# Slave.net
KiCad netlist of a schematic drawn in Altium Designer
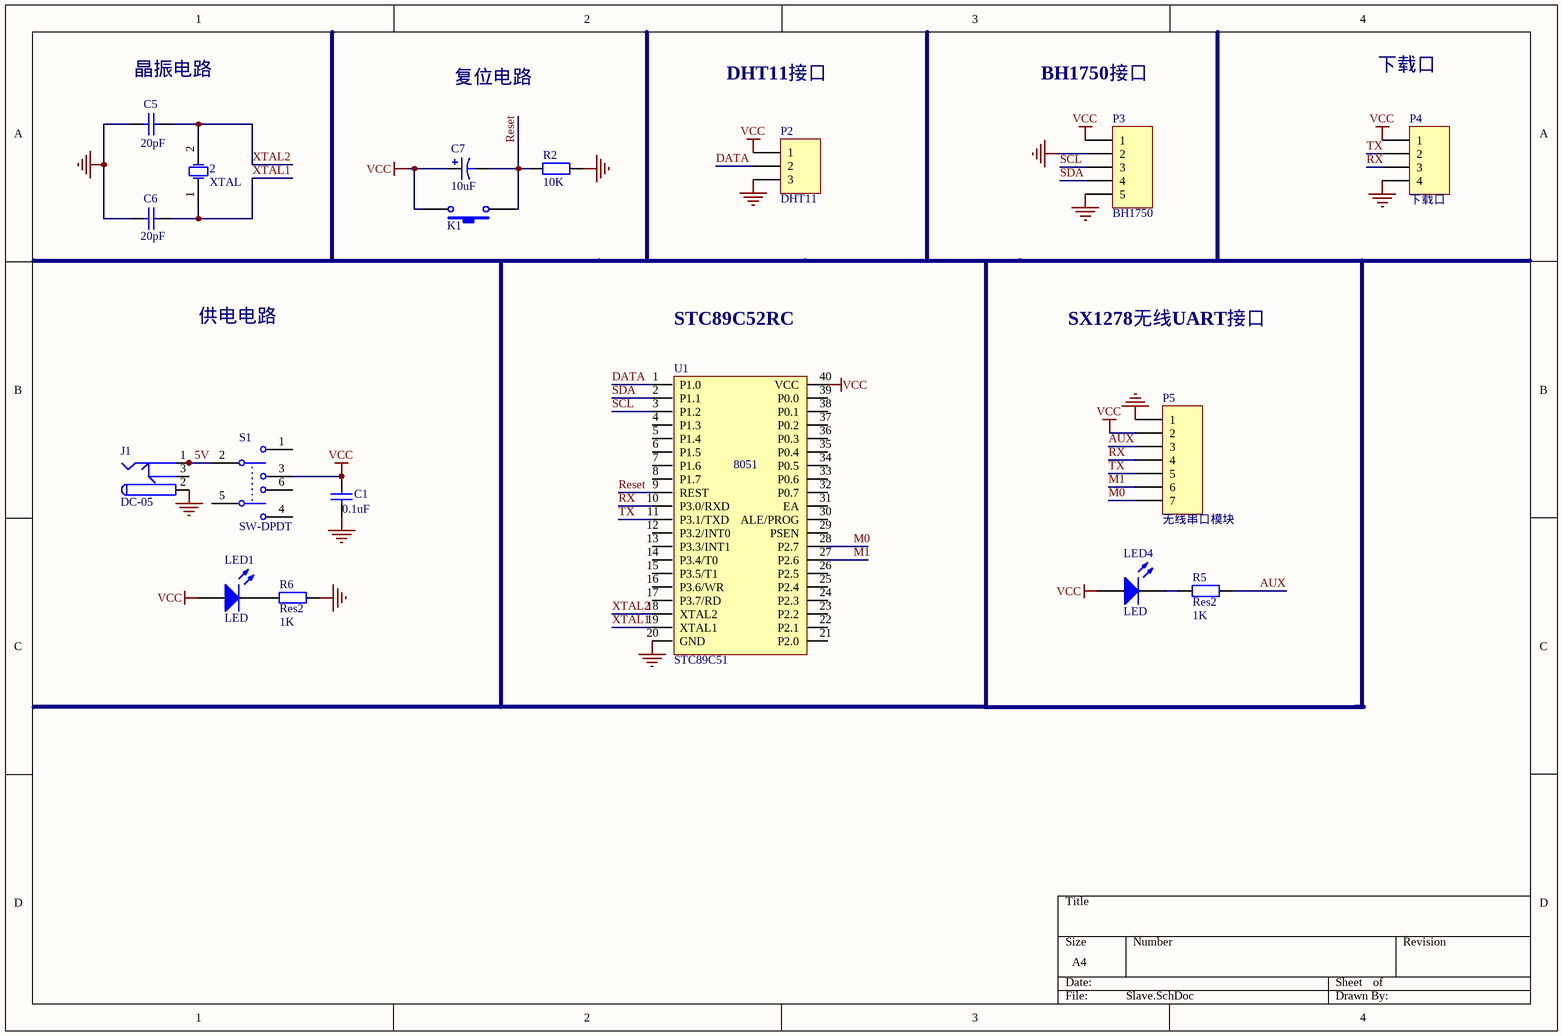
[diagram p0: Slave.SchDoc]

(export (version "E")
  (design (tool "Eeschema 10.0.6"))
  (components
    (comp (ref "2")
      (value "XTAL")
      (footprint "XTAL_US")
      (description "Crystal Oscillator")
      (fields (field (name "PUBLISHER") "Altium Limited"))
      (libsource (lib "Miscellaneous Devices") (part "XTAL"))
    )
    (comp (ref "C1")
      (value "0.1uF")
      (footprint "RAD-0.1")
      (description "Capacitor")
      (fields (field (name "Comment") "Cap") (field (name "PUBLISHER") "Altium Limited"))
      (libsource (lib "Miscellaneous Devices") (part "Cap"))
    )
    (comp (ref "C5")
      (value "20pF")
      (footprint "RAD-0.1")
      (description "Capacitor")
      (fields (field (name "Comment") "Cap") (field (name "PUBLISHER") "Altium Limited"))
      (libsource (lib "Miscellaneous Devices") (part "Cap"))
    )
    (comp (ref "C6")
      (value "20pF")
      (footprint "RAD-0.1")
      (description "Capacitor")
      (fields (field (name "Comment") "Cap") (field (name "PUBLISHER") "Altium Limited"))
      (libsource (lib "Miscellaneous Devices") (part "Cap"))
    )
    (comp (ref "C7")
      (value "10uF")
      (footprint "RB.1/.2")
      (description "Polarized Capacitor (Radial)")
      (fields (field (name "Comment") "Cap Pol1") (field (name "PUBLISHER") "Altium Limited"))
      (libsource (lib "Miscellaneous Devices") (part "Cap Pol1"))
    )
    (comp (ref "J1") (value "DC-05") (footprint "DC-05") (libsource (lib "My library") (part "DC-05")))
    (comp (ref "K1") (value "四脚按键") (footprint "四脚按键") (libsource (lib "My library") (part "四脚按键")))
    (comp (ref "LED1") (value "LED") (footprint "LED") (libsource (lib "My library") (part "LED")))
    (comp (ref "LED4") (value "LED") (footprint "LED") (libsource (lib "My library") (part "LED")))
    (comp (ref "P2")
      (value "DHT11")
      (footprint "HDR1X3")
      (description "Header, 3-Pin")
      (fields (field (name "PUBLISHER") "Altium Limited"))
      (libsource (lib "Miscellaneous Connectors") (part "Header 3"))
    )
    (comp (ref "P3")
      (value "BH1750")
      (footprint "HDR1X5")
      (description "Header, 5-Pin")
      (fields (field (name "PUBLISHER") "Altium Limited"))
      (libsource (lib "Miscellaneous Connectors") (part "Header 5"))
    )
    (comp (ref "P4")
      (value "下载口")
      (footprint "HDR1X4")
      (description "Header, 4-Pin")
      (fields (field (name "PUBLISHER") "Altium Limited"))
      (libsource (lib "Miscellaneous Connectors") (part "Header 4"))
    )
    (comp (ref "P5")
      (value "无线串口模块")
      (footprint "AS32-TTL-100")
      (description "Header, 7-Pin")
      (fields (field (name "PUBLISHER") "Altium Limited"))
      (libsource (lib "Miscellaneous Connectors") (part "Header 7"))
    )
    (comp (ref "R2")
      (value "10K")
      (footprint "AXIAL-0.4")
      (description "Resistor")
      (fields (field (name "Comment") "Res2") (field (name "PUBLISHER") "Altium Limited"))
      (libsource (lib "Miscellaneous Devices") (part "Res2"))
    )
    (comp (ref "R5")
      (value "Res2")
      (footprint "AXIAL-0.4")
      (description "Resistor")
      (fields (field (name "ALTIUM_VALUE") "1K") (field (name "PUBLISHER") "Altium Limited"))
      (libsource (lib "Miscellaneous Devices") (part "Res2"))
    )
    (comp (ref "R6")
      (value "Res2")
      (footprint "AXIAL-0.4")
      (description "Resistor")
      (fields (field (name "ALTIUM_VALUE") "1K") (field (name "PUBLISHER") "Altium Limited"))
      (libsource (lib "Miscellaneous Devices") (part "Res2"))
    )
    (comp (ref "S1")
      (value "SW-DPDT")
      (footprint "SWITCH_B1")
      (description "单刀双掷开关")
      (fields (field (name "PUBLISHER") "Altium Limited"))
      (libsource (lib "Fszhang") (part "SW-DPDT"))
    )
    (comp (ref "U1") (value "STC89C51") (footprint "DIP-40") (libsource (lib "My library") (part "STC89C51")))
  )
  (nets
    (net (code "1") (name "/5V") (class "Default")
      (node (ref "J1") (pin "1") (pinfunction "1_1") (pintype "passive"))
      (node (ref "S1") (pin "2") (pinfunction "2_2") (pintype "passive"))
    )
    (net (code "2") (name "/AUX") (class "Default")
      (node (ref "P5") (pin "3") (pinfunction "3_3") (pintype "passive"))
      (node (ref "R5") (pin "2") (pinfunction "2_2") (pintype "passive"))
    )
    (net (code "3") (name "/DATA") (class "Default")
      (node (ref "P2") (pin "2") (pinfunction "2_2") (pintype "passive"))
      (node (ref "U1") (pin "1") (pinfunction "P1.0_1") (pintype "passive"))
    )
    (net (code "4") (name "/M0") (class "Default")
      (node (ref "P5") (pin "7") (pinfunction "7_7") (pintype "passive"))
      (node (ref "U1") (pin "28") (pinfunction "P2.7_28") (pintype "passive"))
    )
    (net (code "5") (name "/M1") (class "Default")
      (node (ref "P5") (pin "6") (pinfunction "6_6") (pintype "passive"))
      (node (ref "U1") (pin "27") (pinfunction "P2.6_27") (pintype "passive"))
    )
    (net (code "6") (name "/RX") (class "Default")
      (node (ref "P4") (pin "3") (pinfunction "3_3") (pintype "passive"))
      (node (ref "P5") (pin "4") (pinfunction "4_4") (pintype "passive"))
      (node (ref "U1") (pin "10") (pinfunction "P3.0/RXD_10") (pintype "passive"))
    )
    (net (code "7") (name "/Reset") (class "Default")
      (node (ref "C7") (pin "2") (pinfunction "2_2") (pintype "passive"))
      (node (ref "K1") (pin "1") (pinfunction "1_1") (pintype "passive"))
      (node (ref "R2") (pin "1") (pinfunction "1_1") (pintype "passive"))
      (node (ref "U1") (pin "9") (pinfunction "REST_9") (pintype "passive"))
    )
    (net (code "8") (name "/SCL") (class "Default")
      (node (ref "P3") (pin "3") (pinfunction "3_3") (pintype "passive"))
      (node (ref "U1") (pin "3") (pinfunction "P1.2_3") (pintype "passive"))
    )
    (net (code "9") (name "/SDA") (class "Default")
      (node (ref "P3") (pin "4") (pinfunction "4_4") (pintype "passive"))
      (node (ref "U1") (pin "2") (pinfunction "P1.1_2") (pintype "passive"))
    )
    (net (code "10") (name "/TX") (class "Default")
      (node (ref "P4") (pin "2") (pinfunction "2_2") (pintype "passive"))
      (node (ref "P5") (pin "5") (pinfunction "5_5") (pintype "passive"))
      (node (ref "U1") (pin "11") (pinfunction "P3.1/TXD_11") (pintype "passive"))
    )
    (net (code "11") (name "/XTAL1") (class "Default")
      (node (ref "2") (pin "1") (pinfunction "OSC1_1") (pintype "passive"))
      (node (ref "C6") (pin "2") (pinfunction "2_2") (pintype "passive"))
      (node (ref "U1") (pin "19") (pinfunction "XTAL1_19") (pintype "passive"))
    )
    (net (code "12") (name "/XTAL2") (class "Default")
      (node (ref "2") (pin "2") (pinfunction "OSC2_2") (pintype "passive"))
      (node (ref "C5") (pin "2") (pinfunction "2_2") (pintype "passive"))
      (node (ref "U1") (pin "18") (pinfunction "XTAL2_18") (pintype "passive"))
    )
    (net (code "13") (name "GND") (class "Default")
      (node (ref "C1") (pin "1") (pinfunction "1_1") (pintype "passive"))
      (node (ref "C5") (pin "1") (pinfunction "1_1") (pintype "passive"))
      (node (ref "C6") (pin "1") (pinfunction "1_1") (pintype "passive"))
      (node (ref "J1") (pin "2") (pinfunction "2_2") (pintype "passive"))
      (node (ref "P2") (pin "3") (pinfunction "3_3") (pintype "passive"))
      (node (ref "P3") (pin "2") (pinfunction "2_2") (pintype "passive"))
      (node (ref "P3") (pin "5") (pinfunction "5_5") (pintype "passive"))
      (node (ref "P4") (pin "4") (pinfunction "4_4") (pintype "passive"))
      (node (ref "P5") (pin "1") (pinfunction "1_1") (pintype "passive"))
      (node (ref "R2") (pin "2") (pinfunction "2_2") (pintype "passive"))
      (node (ref "R6") (pin "2") (pinfunction "2_2") (pintype "passive"))
      (node (ref "U1") (pin "20") (pinfunction "GND_20") (pintype "passive"))
    )
    (net (code "14") (name "Net-(LED1-Pad2)") (class "Default")
      (node (ref "LED1") (pin "2") (pinfunction "2_2") (pintype "passive"))
      (node (ref "R6") (pin "1") (pinfunction "1_1") (pintype "passive"))
    )
    (net (code "15") (name "Net-(LED4-Pad2)") (class "Default")
      (node (ref "LED4") (pin "2") (pinfunction "2_2") (pintype "passive"))
      (node (ref "R5") (pin "1") (pinfunction "1_1") (pintype "passive"))
    )
    (net (code "16") (name "VCC") (class "Default")
      (node (ref "C1") (pin "2") (pinfunction "2_2") (pintype "passive"))
      (node (ref "C7") (pin "1") (pinfunction "1_1") (pintype "passive"))
      (node (ref "K1") (pin "2") (pinfunction "2_2") (pintype "passive"))
      (node (ref "LED1") (pin "1") (pinfunction "1_1") (pintype "passive"))
      (node (ref "LED4") (pin "1") (pinfunction "1_1") (pintype "passive"))
      (node (ref "P2") (pin "1") (pinfunction "1_1") (pintype "passive"))
      (node (ref "P3") (pin "1") (pinfunction "1_1") (pintype "passive"))
      (node (ref "P4") (pin "1") (pinfunction "1_1") (pintype "passive"))
      (node (ref "P5") (pin "2") (pinfunction "2_2") (pintype "passive"))
      (node (ref "S1") (pin "3") (pinfunction "3_3") (pintype "passive"))
      (node (ref "U1") (pin "40") (pinfunction "VCC_40") (pintype "passive"))
    )
    (net (code "17") (name "unconnected-(J1-Pad3)") (class "Default")
      (node (ref "J1") (pin "3") (pinfunction "3_3") (pintype "passive"))
    )
    (net (code "18") (name "unconnected-(S1-Pad1)") (class "Default")
      (node (ref "S1") (pin "1") (pinfunction "1_1") (pintype "passive"))
    )
    (net (code "19") (name "unconnected-(S1-Pad4)") (class "Default")
      (node (ref "S1") (pin "4") (pinfunction "4_4") (pintype "passive"))
    )
    (net (code "20") (name "unconnected-(S1-Pad5)") (class "Default")
      (node (ref "S1") (pin "5") (pinfunction "5_5") (pintype "passive"))
    )
    (net (code "21") (name "unconnected-(S1-Pad6)") (class "Default")
      (node (ref "S1") (pin "6") (pinfunction "6_6") (pintype "passive"))
    )
    (net (code "22") (name "unconnected-(U1-ALE{slash}PROG-Pad30)") (class "Default")
      (node (ref "U1") (pin "30") (pinfunction "ALE/PROG_30") (pintype "passive"))
    )
    (net (code "23") (name "unconnected-(U1-EA-Pad31)") (class "Default")
      (node (ref "U1") (pin "31") (pinfunction "EA_31") (pintype "passive"))
    )
    (net (code "24") (name "unconnected-(U1-P0.0-Pad39)") (class "Default")
      (node (ref "U1") (pin "39") (pinfunction "P0.0_39") (pintype "passive"))
    )
    (net (code "25") (name "unconnected-(U1-P0.1-Pad38)") (class "Default")
      (node (ref "U1") (pin "38") (pinfunction "P0.1_38") (pintype "passive"))
    )
    (net (code "26") (name "unconnected-(U1-P0.2-Pad37)") (class "Default")
      (node (ref "U1") (pin "37") (pinfunction "P0.2_37") (pintype "passive"))
    )
    (net (code "27") (name "unconnected-(U1-P0.3-Pad36)") (class "Default")
      (node (ref "U1") (pin "36") (pinfunction "P0.3_36") (pintype "passive"))
    )
    (net (code "28") (name "unconnected-(U1-P0.4-Pad35)") (class "Default")
      (node (ref "U1") (pin "35") (pinfunction "P0.4_35") (pintype "passive"))
    )
    (net (code "29") (name "unconnected-(U1-P0.5-Pad34)") (class "Default")
      (node (ref "U1") (pin "34") (pinfunction "P0.5_34") (pintype "passive"))
    )
    (net (code "30") (name "unconnected-(U1-P0.6-Pad33)") (class "Default")
      (node (ref "U1") (pin "33") (pinfunction "P0.6_33") (pintype "passive"))
    )
    (net (code "31") (name "unconnected-(U1-P0.7-Pad32)") (class "Default")
      (node (ref "U1") (pin "32") (pinfunction "P0.7_32") (pintype "passive"))
    )
    (net (code "32") (name "unconnected-(U1-P1.3-Pad4)") (class "Default")
      (node (ref "U1") (pin "4") (pinfunction "P1.3_4") (pintype "passive"))
    )
    (net (code "33") (name "unconnected-(U1-P1.4-Pad5)") (class "Default")
      (node (ref "U1") (pin "5") (pinfunction "P1.4_5") (pintype "passive"))
    )
    (net (code "34") (name "unconnected-(U1-P1.5-Pad6)") (class "Default")
      (node (ref "U1") (pin "6") (pinfunction "P1.5_6") (pintype "passive"))
    )
    (net (code "35") (name "unconnected-(U1-P1.6-Pad7)") (class "Default")
      (node (ref "U1") (pin "7") (pinfunction "P1.6_7") (pintype "passive"))
    )
    (net (code "36") (name "unconnected-(U1-P1.7-Pad8)") (class "Default")
      (node (ref "U1") (pin "8") (pinfunction "P1.7_8") (pintype "passive"))
    )
    (net (code "37") (name "unconnected-(U1-P2.0-Pad21)") (class "Default")
      (node (ref "U1") (pin "21") (pinfunction "P2.0_21") (pintype "passive"))
    )
    (net (code "38") (name "unconnected-(U1-P2.1-Pad22)") (class "Default")
      (node (ref "U1") (pin "22") (pinfunction "P2.1_22") (pintype "passive"))
    )
    (net (code "39") (name "unconnected-(U1-P2.2-Pad23)") (class "Default")
      (node (ref "U1") (pin "23") (pinfunction "P2.2_23") (pintype "passive"))
    )
    (net (code "40") (name "unconnected-(U1-P2.3-Pad24)") (class "Default")
      (node (ref "U1") (pin "24") (pinfunction "P2.3_24") (pintype "passive"))
    )
    (net (code "41") (name "unconnected-(U1-P2.4-Pad25)") (class "Default")
      (node (ref "U1") (pin "25") (pinfunction "P2.4_25") (pintype "passive"))
    )
    (net (code "42") (name "unconnected-(U1-P2.5-Pad26)") (class "Default")
      (node (ref "U1") (pin "26") (pinfunction "P2.5_26") (pintype "passive"))
    )
    (net (code "43") (name "unconnected-(U1-P3.2{slash}INT0-Pad12)") (class "Default")
      (node (ref "U1") (pin "12") (pinfunction "P3.2/INT0_12") (pintype "passive"))
    )
    (net (code "44") (name "unconnected-(U1-P3.3{slash}INT1-Pad13)") (class "Default")
      (node (ref "U1") (pin "13") (pinfunction "P3.3/INT1_13") (pintype "passive"))
    )
    (net (code "45") (name "unconnected-(U1-P3.4{slash}T0-Pad14)") (class "Default")
      (node (ref "U1") (pin "14") (pinfunction "P3.4/T0_14") (pintype "passive"))
    )
    (net (code "46") (name "unconnected-(U1-P3.5{slash}T1-Pad15)") (class "Default")
      (node (ref "U1") (pin "15") (pinfunction "P3.5/T1_15") (pintype "passive"))
    )
    (net (code "47") (name "unconnected-(U1-P3.6{slash}WR-Pad16)") (class "Default")
      (node (ref "U1") (pin "16") (pinfunction "P3.6/WR_16") (pintype "passive"))
    )
    (net (code "48") (name "unconnected-(U1-P3.7{slash}RD-Pad17)") (class "Default")
      (node (ref "U1") (pin "17") (pinfunction "P3.7/RD_17") (pintype "passive"))
    )
    (net (code "49") (name "unconnected-(U1-PSEN-Pad29)") (class "Default")
      (node (ref "U1") (pin "29") (pinfunction "PSEN_29") (pintype "passive"))
    )
  )
)
